# SimulatorT2InterfaceRevC.net
KiCad netlist of a schematic drawn in EAGLE
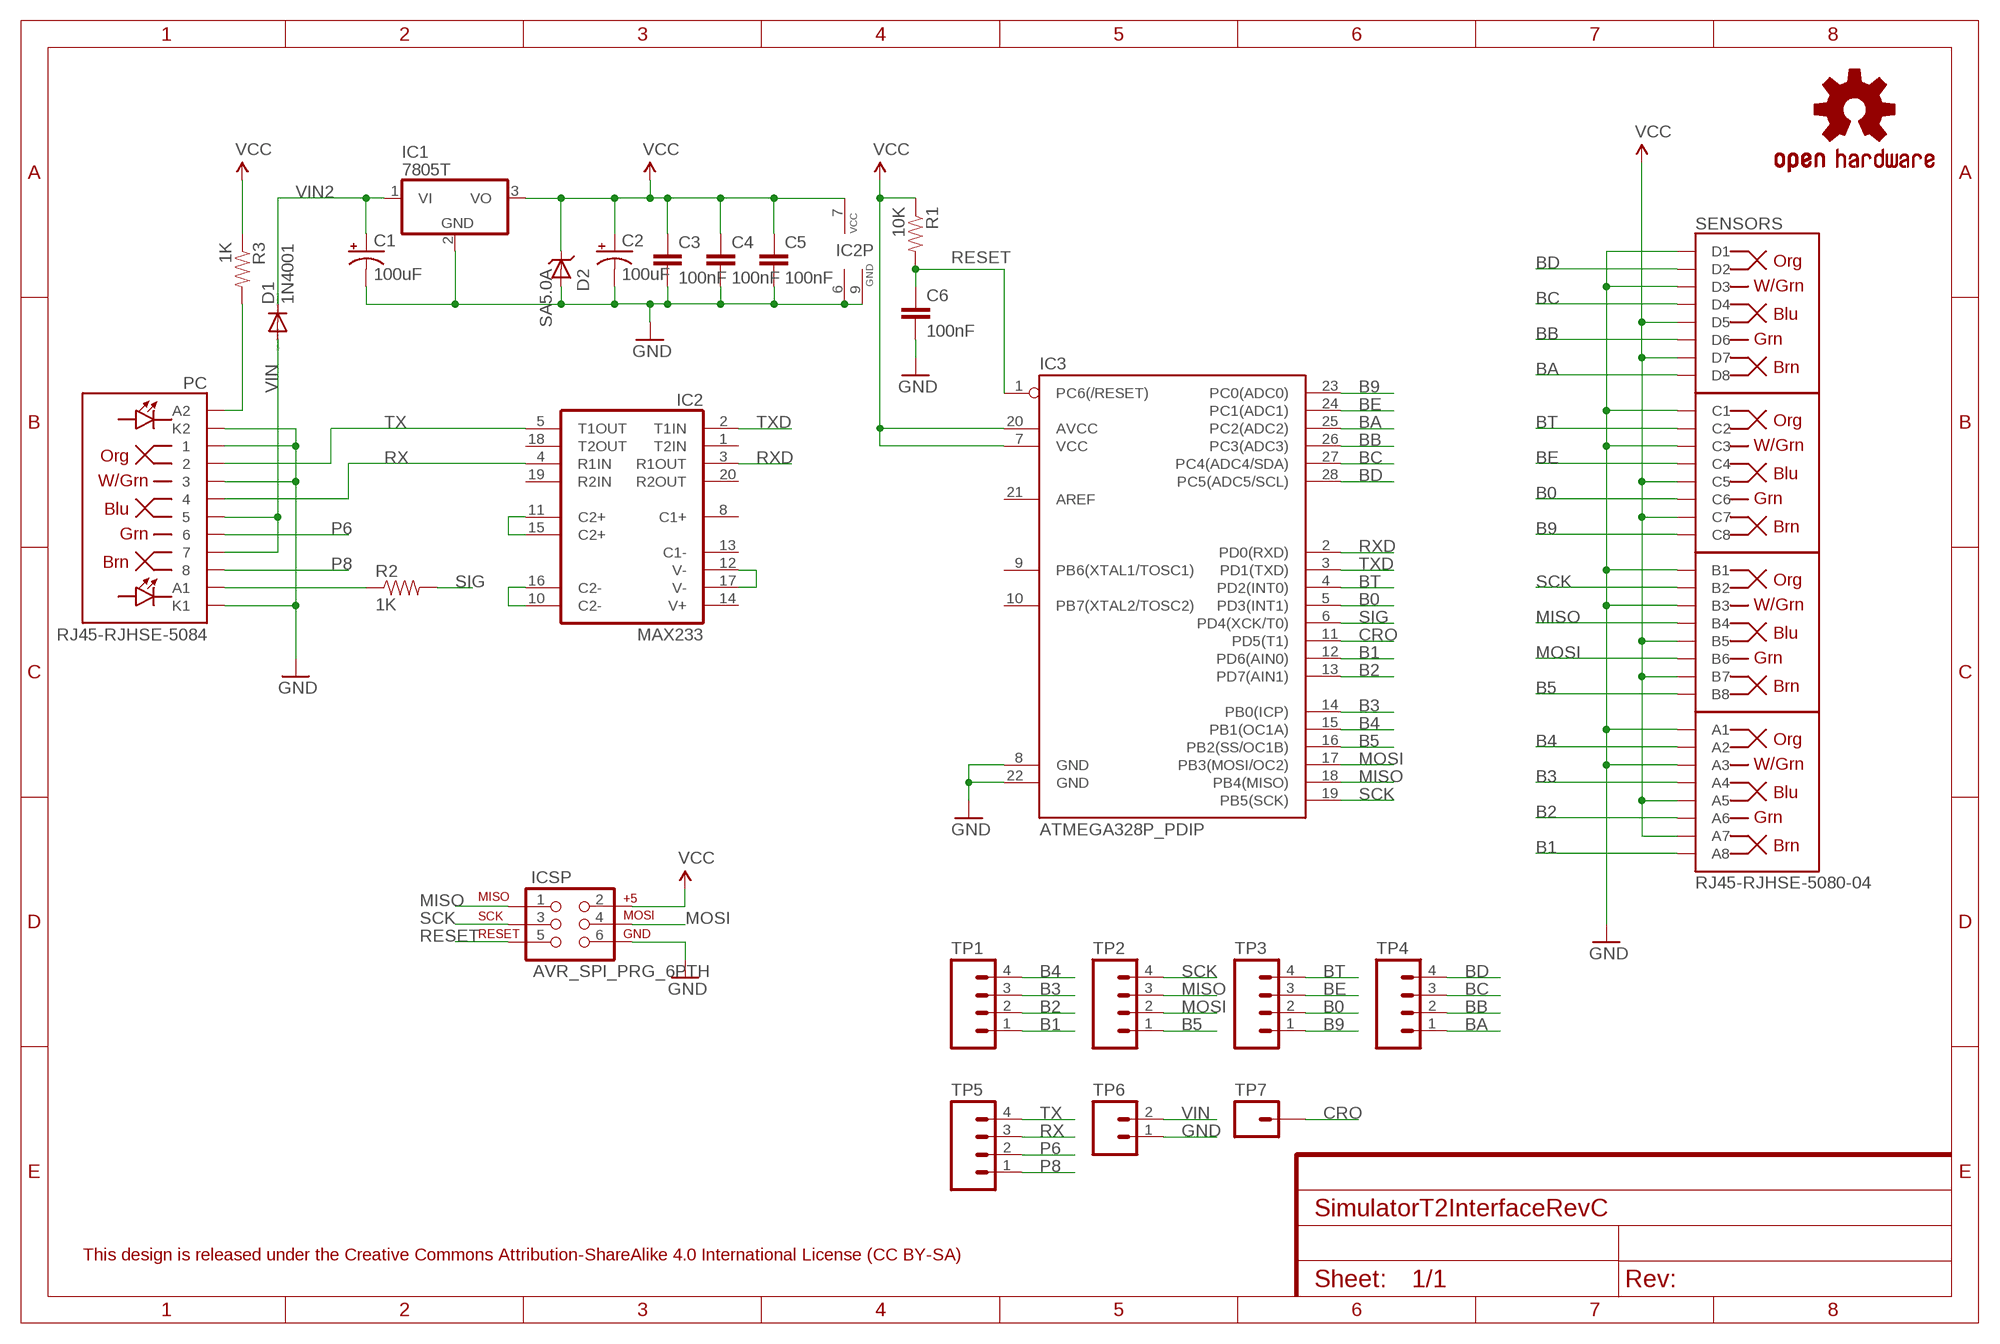
[diagram p0: schematic, sheet 1]

(export (version "E")
  (design (tool "Eeschema 10.0.6"))
  (components
    (comp (ref "C1")
      (value "100uF")
      (footprint "eagle-import:CPOL-RADIAL-100UF-25V")
      (libsource (lib "eagle-import") (part "CAP_POLPTH1"))
    )
    (comp (ref "C2")
      (value "100uF")
      (footprint "eagle-import:CPOL-RADIAL-100UF-25V")
      (libsource (lib "eagle-import") (part "CAP_POLPTH1"))
    )
    (comp (ref "C3")
      (value "100nF")
      (footprint "eagle-import:CAP-PTH-SMALL")
      (libsource (lib "eagle-import") (part "CAPPTH"))
    )
    (comp (ref "C4")
      (value "100nF")
      (footprint "eagle-import:CAP-PTH-SMALL")
      (libsource (lib "eagle-import") (part "CAPPTH"))
    )
    (comp (ref "C5")
      (value "100nF")
      (footprint "eagle-import:CAP-PTH-SMALL")
      (libsource (lib "eagle-import") (part "CAPPTH"))
    )
    (comp (ref "C6")
      (value "100nF")
      (footprint "eagle-import:CAP-PTH-SMALL")
      (libsource (lib "eagle-import") (part "CAPPTH"))
    )
    (comp (ref "D1")
      (value "1N4001")
      (footprint "eagle-import:DO41_DIODE")
      (libsource (lib "eagle-import") (part "1N4001"))
    )
    (comp (ref "D2")
      (value "SA5.0A")
      (footprint "eagle-import:DO41_TVS_UNI")
      (libsource (lib "eagle-import") (part "SA5.0A"))
    )
    (comp (ref "IC1")
      (value "7805T")
      (footprint "eagle-import:TO220H")
      (libsource (lib "eagle-import") (part "78T05"))
    )
    (comp (ref "IC2")
      (value "MAX233")
      (footprint "eagle-import:DIL20")
      (fields (field (name "MPN") "MAX233ACPP+G36"))
      (libsource (lib "eagle-import") (part "MAX233"))
    )
    (comp (ref "IC3")
      (value "ATMEGA328P_PDIP")
      (footprint "eagle-import:DIL28-3")
      (libsource (lib "eagle-import") (part "ATMEGA328P_PDIP"))
    )
    (comp (ref "ICSP")
      (value "AVR_SPI_PRG_6PTH")
      (footprint "eagle-import:2X3")
      (libsource (lib "eagle-import") (part "AVR_SPI_PRG_6PTH"))
    )
    (comp (ref "LOGO1")
      (value "OSHW-LOGOS")
      (footprint "eagle-import:OSHW-LOGO-S")
      (libsource (lib "eagle-import") (part "OSHW-LOGOS"))
    )
    (comp (ref "PC")
      (value "RJ45-RJHSE-5084")
      (footprint "eagle-import:RJ45-RJHSE-5084")
      (libsource (lib "eagle-import") (part "RJ45-RJHSE-5084"))
    )
    (comp (ref "R1")
      (value "10K")
      (footprint "eagle-import:AXIAL-0.4")
      (libsource (lib "eagle-import") (part "RESISTORPTH-1/4W"))
    )
    (comp (ref "R2")
      (value "1K")
      (footprint "eagle-import:AXIAL-0.4")
      (libsource (lib "eagle-import") (part "RESISTORPTH-1/4W"))
    )
    (comp (ref "R3")
      (value "1K")
      (footprint "eagle-import:AXIAL-0.4")
      (libsource (lib "eagle-import") (part "RESISTORPTH-1/4W"))
    )
    (comp (ref "SENSORS")
      (value "RJ45-RJHSE-5080-04")
      (footprint "eagle-import:RJ45-RJHSE-5080-04")
      (libsource (lib "eagle-import") (part "RJ45-RJHSE-5080-04"))
    )
    (comp (ref "TP1")
      (value "M04PTH")
      (footprint "eagle-import:1X04")
      (libsource (lib "eagle-import") (part "M04PTH"))
    )
    (comp (ref "TP2")
      (value "M04PTH")
      (footprint "eagle-import:1X04")
      (libsource (lib "eagle-import") (part "M04PTH"))
    )
    (comp (ref "TP3")
      (value "M04PTH")
      (footprint "eagle-import:1X04")
      (libsource (lib "eagle-import") (part "M04PTH"))
    )
    (comp (ref "TP4")
      (value "M04PTH")
      (footprint "eagle-import:1X04")
      (libsource (lib "eagle-import") (part "M04PTH"))
    )
    (comp (ref "TP5")
      (value "M04PTH")
      (footprint "eagle-import:1X04")
      (libsource (lib "eagle-import") (part "M04PTH"))
    )
    (comp (ref "TP6")
      (value "M02PTH")
      (footprint "eagle-import:1X02")
      (libsource (lib "eagle-import") (part "M02PTH"))
    )
    (comp (ref "TP7")
      (value "M01PTH")
      (footprint "eagle-import:1X01")
      (libsource (lib "eagle-import") (part "M01PTH"))
    )
  )
  (nets
    (net (code "1") (name "/B0") (class "Default")
      (node (ref "IC3") (pin "5") (pinfunction "PD3(INT1)_5") (pintype "bidirectional"))
      (node (ref "SENSORS") (pin "C6") (pinfunction "C6_C6") (pintype "bidirectional"))
      (node (ref "TP3") (pin "2") (pinfunction "2_2") (pintype "passive"))
    )
    (net (code "2") (name "/B1") (class "Default")
      (node (ref "IC3") (pin "12") (pinfunction "PD6(AIN0)_12") (pintype "bidirectional"))
      (node (ref "SENSORS") (pin "A8") (pinfunction "A8_A8") (pintype "bidirectional"))
      (node (ref "TP1") (pin "1") (pinfunction "1_1") (pintype "passive"))
    )
    (net (code "3") (name "/B2") (class "Default")
      (node (ref "IC3") (pin "13") (pinfunction "PD7(AIN1)_13") (pintype "bidirectional"))
      (node (ref "SENSORS") (pin "A6") (pinfunction "A6_A6") (pintype "bidirectional"))
      (node (ref "TP1") (pin "2") (pinfunction "2_2") (pintype "passive"))
    )
    (net (code "4") (name "/B3") (class "Default")
      (node (ref "IC3") (pin "14") (pinfunction "PB0(ICP)_14") (pintype "bidirectional"))
      (node (ref "SENSORS") (pin "A4") (pinfunction "A4_A4") (pintype "bidirectional"))
      (node (ref "TP1") (pin "3") (pinfunction "3_3") (pintype "passive"))
    )
    (net (code "5") (name "/B4") (class "Default")
      (node (ref "IC3") (pin "15") (pinfunction "PB1(OC1A)_15") (pintype "bidirectional"))
      (node (ref "SENSORS") (pin "A2") (pinfunction "A2_A2") (pintype "bidirectional"))
      (node (ref "TP1") (pin "4") (pinfunction "4_4") (pintype "passive"))
    )
    (net (code "6") (name "/B5") (class "Default")
      (node (ref "IC3") (pin "16") (pinfunction "PB2(SS/OC1B)_16") (pintype "bidirectional"))
      (node (ref "SENSORS") (pin "B8") (pinfunction "B8_B8") (pintype "bidirectional"))
      (node (ref "TP2") (pin "1") (pinfunction "1_1") (pintype "passive"))
    )
    (net (code "7") (name "/B9") (class "Default")
      (node (ref "IC3") (pin "23") (pinfunction "PC0(ADC0)_23") (pintype "bidirectional"))
      (node (ref "SENSORS") (pin "C8") (pinfunction "C8_C8") (pintype "bidirectional"))
      (node (ref "TP3") (pin "1") (pinfunction "1_1") (pintype "passive"))
    )
    (net (code "8") (name "/BA") (class "Default")
      (node (ref "IC3") (pin "25") (pinfunction "PC2(ADC2)_25") (pintype "bidirectional"))
      (node (ref "SENSORS") (pin "D8") (pinfunction "D8_D8") (pintype "bidirectional"))
      (node (ref "TP4") (pin "1") (pinfunction "1_1") (pintype "passive"))
    )
    (net (code "9") (name "/BB") (class "Default")
      (node (ref "IC3") (pin "26") (pinfunction "PC3(ADC3)_26") (pintype "bidirectional"))
      (node (ref "SENSORS") (pin "D6") (pinfunction "D6_D6") (pintype "bidirectional"))
      (node (ref "TP4") (pin "2") (pinfunction "2_2") (pintype "passive"))
    )
    (net (code "10") (name "/BC") (class "Default")
      (node (ref "IC3") (pin "27") (pinfunction "PC4(ADC4/SDA)_27") (pintype "bidirectional"))
      (node (ref "SENSORS") (pin "D4") (pinfunction "D4_D4") (pintype "bidirectional"))
      (node (ref "TP4") (pin "3") (pinfunction "3_3") (pintype "passive"))
    )
    (net (code "11") (name "/BD") (class "Default")
      (node (ref "IC3") (pin "28") (pinfunction "PC5(ADC5/SCL)_28") (pintype "bidirectional"))
      (node (ref "SENSORS") (pin "D2") (pinfunction "D2_D2") (pintype "bidirectional"))
      (node (ref "TP4") (pin "4") (pinfunction "4_4") (pintype "passive"))
    )
    (net (code "12") (name "/BE") (class "Default")
      (node (ref "IC3") (pin "24") (pinfunction "PC1(ADC1)_24") (pintype "bidirectional"))
      (node (ref "SENSORS") (pin "C4") (pinfunction "C4_C4") (pintype "bidirectional"))
      (node (ref "TP3") (pin "3") (pinfunction "3_3") (pintype "passive"))
    )
    (net (code "13") (name "/BT") (class "Default")
      (node (ref "IC3") (pin "4") (pinfunction "PD2(INT0)_4") (pintype "bidirectional"))
      (node (ref "SENSORS") (pin "C2") (pinfunction "C2_C2") (pintype "bidirectional"))
      (node (ref "TP3") (pin "4") (pinfunction "4_4") (pintype "passive"))
    )
    (net (code "14") (name "/CRO") (class "Default")
      (node (ref "IC3") (pin "11") (pinfunction "PD5(T1)_11") (pintype "bidirectional"))
      (node (ref "TP7") (pin "1") (pinfunction "1_1") (pintype "passive"))
    )
    (net (code "15") (name "/MISO") (class "Default")
      (node (ref "IC3") (pin "18") (pinfunction "PB4(MISO)_18") (pintype "bidirectional"))
      (node (ref "ICSP") (pin "1") (pinfunction "1_1") (pintype "passive"))
      (node (ref "SENSORS") (pin "B4") (pinfunction "B4_B4") (pintype "bidirectional"))
      (node (ref "TP2") (pin "3") (pinfunction "3_3") (pintype "passive"))
    )
    (net (code "16") (name "/MOSI") (class "Default")
      (node (ref "IC3") (pin "17") (pinfunction "PB3(MOSI/OC2)_17") (pintype "bidirectional"))
      (node (ref "ICSP") (pin "4") (pinfunction "4_4") (pintype "passive"))
      (node (ref "SENSORS") (pin "B6") (pinfunction "B6_B6") (pintype "bidirectional"))
      (node (ref "TP2") (pin "2") (pinfunction "2_2") (pintype "passive"))
    )
    (net (code "17") (name "/P6") (class "Default")
      (node (ref "PC") (pin "6") (pinfunction "6_6") (pintype "bidirectional"))
      (node (ref "TP5") (pin "2") (pinfunction "2_2") (pintype "passive"))
    )
    (net (code "18") (name "/P8") (class "Default")
      (node (ref "PC") (pin "8") (pinfunction "8_8") (pintype "bidirectional"))
      (node (ref "TP5") (pin "1") (pinfunction "1_1") (pintype "passive"))
    )
    (net (code "19") (name "/RESET") (class "Default")
      (node (ref "C6") (pin "1") (pinfunction "1_1") (pintype "passive"))
      (node (ref "IC3") (pin "1") (pinfunction "PC6(/RESET)_1") (pintype "bidirectional"))
      (node (ref "ICSP") (pin "5") (pinfunction "5_5") (pintype "passive"))
      (node (ref "R1") (pin "P$2") (pinfunction "2_P$2") (pintype "passive"))
    )
    (net (code "20") (name "/RX") (class "Default")
      (node (ref "IC2") (pin "4") (pinfunction "R1IN_4") (pintype "input"))
      (node (ref "PC") (pin "4") (pinfunction "4_4") (pintype "bidirectional"))
      (node (ref "TP5") (pin "3") (pinfunction "3_3") (pintype "passive"))
    )
    (net (code "21") (name "/RXD") (class "Default")
      (node (ref "IC2") (pin "3") (pinfunction "R1OUT_3") (pintype "output"))
      (node (ref "IC3") (pin "2") (pinfunction "PD0(RXD)_2") (pintype "bidirectional"))
    )
    (net (code "22") (name "/SCK") (class "Default")
      (node (ref "IC3") (pin "19") (pinfunction "PB5(SCK)_19") (pintype "bidirectional"))
      (node (ref "ICSP") (pin "3") (pinfunction "3_3") (pintype "passive"))
      (node (ref "SENSORS") (pin "B2") (pinfunction "B2_B2") (pintype "bidirectional"))
      (node (ref "TP2") (pin "4") (pinfunction "4_4") (pintype "passive"))
    )
    (net (code "23") (name "/SIG") (class "Default")
      (node (ref "IC3") (pin "6") (pinfunction "PD4(XCK/T0)_6") (pintype "bidirectional"))
      (node (ref "R2") (pin "P$2") (pinfunction "2_P$2") (pintype "passive"))
    )
    (net (code "24") (name "/TX") (class "Default")
      (node (ref "IC2") (pin "5") (pinfunction "T1OUT_5") (pintype "output"))
      (node (ref "PC") (pin "2") (pinfunction "2_2") (pintype "bidirectional"))
      (node (ref "TP5") (pin "4") (pinfunction "4_4") (pintype "passive"))
    )
    (net (code "25") (name "/TXD") (class "Default")
      (node (ref "IC2") (pin "2") (pinfunction "T1IN_2") (pintype "input"))
      (node (ref "IC3") (pin "3") (pinfunction "PD1(TXD)_3") (pintype "bidirectional"))
    )
    (net (code "26") (name "/VIN") (class "Default")
      (node (ref "D1") (pin "A") (pinfunction "A_A") (pintype "passive"))
      (node (ref "PC") (pin "5") (pinfunction "5_5") (pintype "bidirectional"))
      (node (ref "PC") (pin "7") (pinfunction "7_7") (pintype "bidirectional"))
      (node (ref "TP6") (pin "2") (pinfunction "2_2") (pintype "passive"))
    )
    (net (code "27") (name "/VIN2") (class "Default")
      (node (ref "C1") (pin "1") (pinfunction "+_1") (pintype "passive"))
      (node (ref "D1") (pin "C") (pinfunction "C_C") (pintype "passive"))
      (node (ref "IC1") (pin "1") (pinfunction "VI_1") (pintype "input"))
    )
    (net (code "28") (name "GND") (class "Default")
      (node (ref "C1") (pin "2") (pinfunction "-_2") (pintype "passive"))
      (node (ref "C2") (pin "2") (pinfunction "-_2") (pintype "passive"))
      (node (ref "C3") (pin "2") (pinfunction "2_2") (pintype "passive"))
      (node (ref "C4") (pin "2") (pinfunction "2_2") (pintype "passive"))
      (node (ref "C5") (pin "2") (pinfunction "2_2") (pintype "passive"))
      (node (ref "C6") (pin "2") (pinfunction "2_2") (pintype "passive"))
      (node (ref "D2") (pin "ANODE") (pinfunction "ANODE_ANODE") (pintype "passive"))
      (node (ref "IC1") (pin "2") (pinfunction "GND_2") (pintype "passive"))
      (node (ref "IC2") (pin "6") (pinfunction "GND_6") (pintype "power_in"))
      (node (ref "IC2") (pin "9") (pinfunction "GND_9") (pintype "power_in"))
      (node (ref "IC3") (pin "22") (pinfunction "GND_22") (pintype "bidirectional"))
      (node (ref "IC3") (pin "8") (pinfunction "GND_8") (pintype "bidirectional"))
      (node (ref "ICSP") (pin "6") (pinfunction "6_6") (pintype "passive"))
      (node (ref "PC") (pin "1") (pinfunction "1_1") (pintype "bidirectional"))
      (node (ref "PC") (pin "3") (pinfunction "3_3") (pintype "bidirectional"))
      (node (ref "PC") (pin "K1") (pinfunction "K1_K1") (pintype "passive"))
      (node (ref "PC") (pin "K2") (pinfunction "K2_K2") (pintype "passive"))
      (node (ref "SENSORS") (pin "A1") (pinfunction "A1_A1") (pintype "bidirectional"))
      (node (ref "SENSORS") (pin "A3") (pinfunction "A3_A3") (pintype "bidirectional"))
      (node (ref "SENSORS") (pin "B1") (pinfunction "B1_B1") (pintype "bidirectional"))
      (node (ref "SENSORS") (pin "B3") (pinfunction "B3_B3") (pintype "bidirectional"))
      (node (ref "SENSORS") (pin "C1") (pinfunction "C1_C1") (pintype "bidirectional"))
      (node (ref "SENSORS") (pin "C3") (pinfunction "C3_C3") (pintype "bidirectional"))
      (node (ref "SENSORS") (pin "D1") (pinfunction "D1_D1") (pintype "bidirectional"))
      (node (ref "SENSORS") (pin "D3") (pinfunction "D3_D3") (pintype "bidirectional"))
      (node (ref "TP6") (pin "1") (pinfunction "1_1") (pintype "passive"))
    )
    (net (code "29") (name "Net-(IC2A-C2+-Pad11)") (class "Default")
      (node (ref "IC2") (pin "11") (pinfunction "C2+_11") (pintype "bidirectional"))
      (node (ref "IC2") (pin "15") (pinfunction "C2+_15") (pintype "bidirectional"))
    )
    (net (code "30") (name "Net-(IC2A-C2--Pad10)") (class "Default")
      (node (ref "IC2") (pin "10") (pinfunction "C2-_10") (pintype "bidirectional"))
      (node (ref "IC2") (pin "16") (pinfunction "C2-_16") (pintype "bidirectional"))
    )
    (net (code "31") (name "Net-(IC2A-V--Pad12)") (class "Default")
      (node (ref "IC2") (pin "12") (pinfunction "V-_12") (pintype "bidirectional"))
      (node (ref "IC2") (pin "17") (pinfunction "V-_17") (pintype "bidirectional"))
    )
    (net (code "32") (name "Net-(R2-1)") (class "Default")
      (node (ref "PC") (pin "A1") (pinfunction "A1_A1") (pintype "passive"))
      (node (ref "R2") (pin "P$1") (pinfunction "1_P$1") (pintype "passive"))
    )
    (net (code "33") (name "Net-(R3-2)") (class "Default")
      (node (ref "PC") (pin "A2") (pinfunction "A2_A2") (pintype "passive"))
      (node (ref "R3") (pin "P$2") (pinfunction "2_P$2") (pintype "passive"))
    )
    (net (code "34") (name "VCC") (class "Default")
      (node (ref "C2") (pin "1") (pinfunction "+_1") (pintype "passive"))
      (node (ref "C3") (pin "1") (pinfunction "1_1") (pintype "passive"))
      (node (ref "C4") (pin "1") (pinfunction "1_1") (pintype "passive"))
      (node (ref "C5") (pin "1") (pinfunction "1_1") (pintype "passive"))
      (node (ref "D2") (pin "CATHODE") (pinfunction "CATHODE_CATHODE") (pintype "passive"))
      (node (ref "IC1") (pin "3") (pinfunction "VO_3") (pintype "passive"))
      (node (ref "IC2") (pin "7") (pinfunction "VCC_7") (pintype "power_in"))
      (node (ref "IC3") (pin "20") (pinfunction "AVCC_20") (pintype "bidirectional"))
      (node (ref "IC3") (pin "7") (pinfunction "VCC_7") (pintype "bidirectional"))
      (node (ref "ICSP") (pin "2") (pinfunction "2_2") (pintype "passive"))
      (node (ref "R1") (pin "P$1") (pinfunction "1_P$1") (pintype "passive"))
      (node (ref "R3") (pin "P$1") (pinfunction "1_P$1") (pintype "passive"))
      (node (ref "SENSORS") (pin "A5") (pinfunction "A5_A5") (pintype "bidirectional"))
      (node (ref "SENSORS") (pin "A7") (pinfunction "A7_A7") (pintype "bidirectional"))
      (node (ref "SENSORS") (pin "B5") (pinfunction "B5_B5") (pintype "bidirectional"))
      (node (ref "SENSORS") (pin "B7") (pinfunction "B7_B7") (pintype "bidirectional"))
      (node (ref "SENSORS") (pin "C5") (pinfunction "C5_C5") (pintype "bidirectional"))
      (node (ref "SENSORS") (pin "C7") (pinfunction "C7_C7") (pintype "bidirectional"))
      (node (ref "SENSORS") (pin "D5") (pinfunction "D5_D5") (pintype "bidirectional"))
      (node (ref "SENSORS") (pin "D7") (pinfunction "D7_D7") (pintype "bidirectional"))
    )
    (net (code "35") (name "unconnected-(IC2A-C1+-Pad8)") (class "Default")
      (node (ref "IC2") (pin "8") (pinfunction "C1+_8") (pintype "bidirectional"))
    )
    (net (code "36") (name "unconnected-(IC2A-C1--Pad13)") (class "Default")
      (node (ref "IC2") (pin "13") (pinfunction "C1-_13") (pintype "bidirectional"))
    )
    (net (code "37") (name "unconnected-(IC2A-R2IN-Pad19)") (class "Default")
      (node (ref "IC2") (pin "19") (pinfunction "R2IN_19") (pintype "input"))
    )
    (net (code "38") (name "unconnected-(IC2A-R2OUT-Pad20)") (class "Default")
      (node (ref "IC2") (pin "20") (pinfunction "R2OUT_20") (pintype "output"))
    )
    (net (code "39") (name "unconnected-(IC2A-T2IN-Pad1)") (class "Default")
      (node (ref "IC2") (pin "1") (pinfunction "T2IN_1") (pintype "input"))
    )
    (net (code "40") (name "unconnected-(IC2A-T2OUT-Pad18)") (class "Default")
      (node (ref "IC2") (pin "18") (pinfunction "T2OUT_18") (pintype "output"))
    )
    (net (code "41") (name "unconnected-(IC2A-V+-Pad14)") (class "Default")
      (node (ref "IC2") (pin "14") (pinfunction "V+_14") (pintype "bidirectional"))
    )
    (net (code "42") (name "unconnected-(IC3-AREF-Pad21)") (class "Default")
      (node (ref "IC3") (pin "21") (pinfunction "AREF_21") (pintype "bidirectional"))
    )
    (net (code "43") (name "unconnected-(IC3-PB6(XTAL1{slash}TOSC1)-Pad9)") (class "Default")
      (node (ref "IC3") (pin "9") (pinfunction "PB6(XTAL1/TOSC1)_9") (pintype "bidirectional"))
    )
    (net (code "44") (name "unconnected-(IC3-PB7(XTAL2{slash}TOSC2)-Pad10)") (class "Default")
      (node (ref "IC3") (pin "10") (pinfunction "PB7(XTAL2/TOSC2)_10") (pintype "bidirectional"))
    )
  )
)
